# MCU009A_EmuInterface.net
KiCad netlist of a schematic drawn in Altium Designer
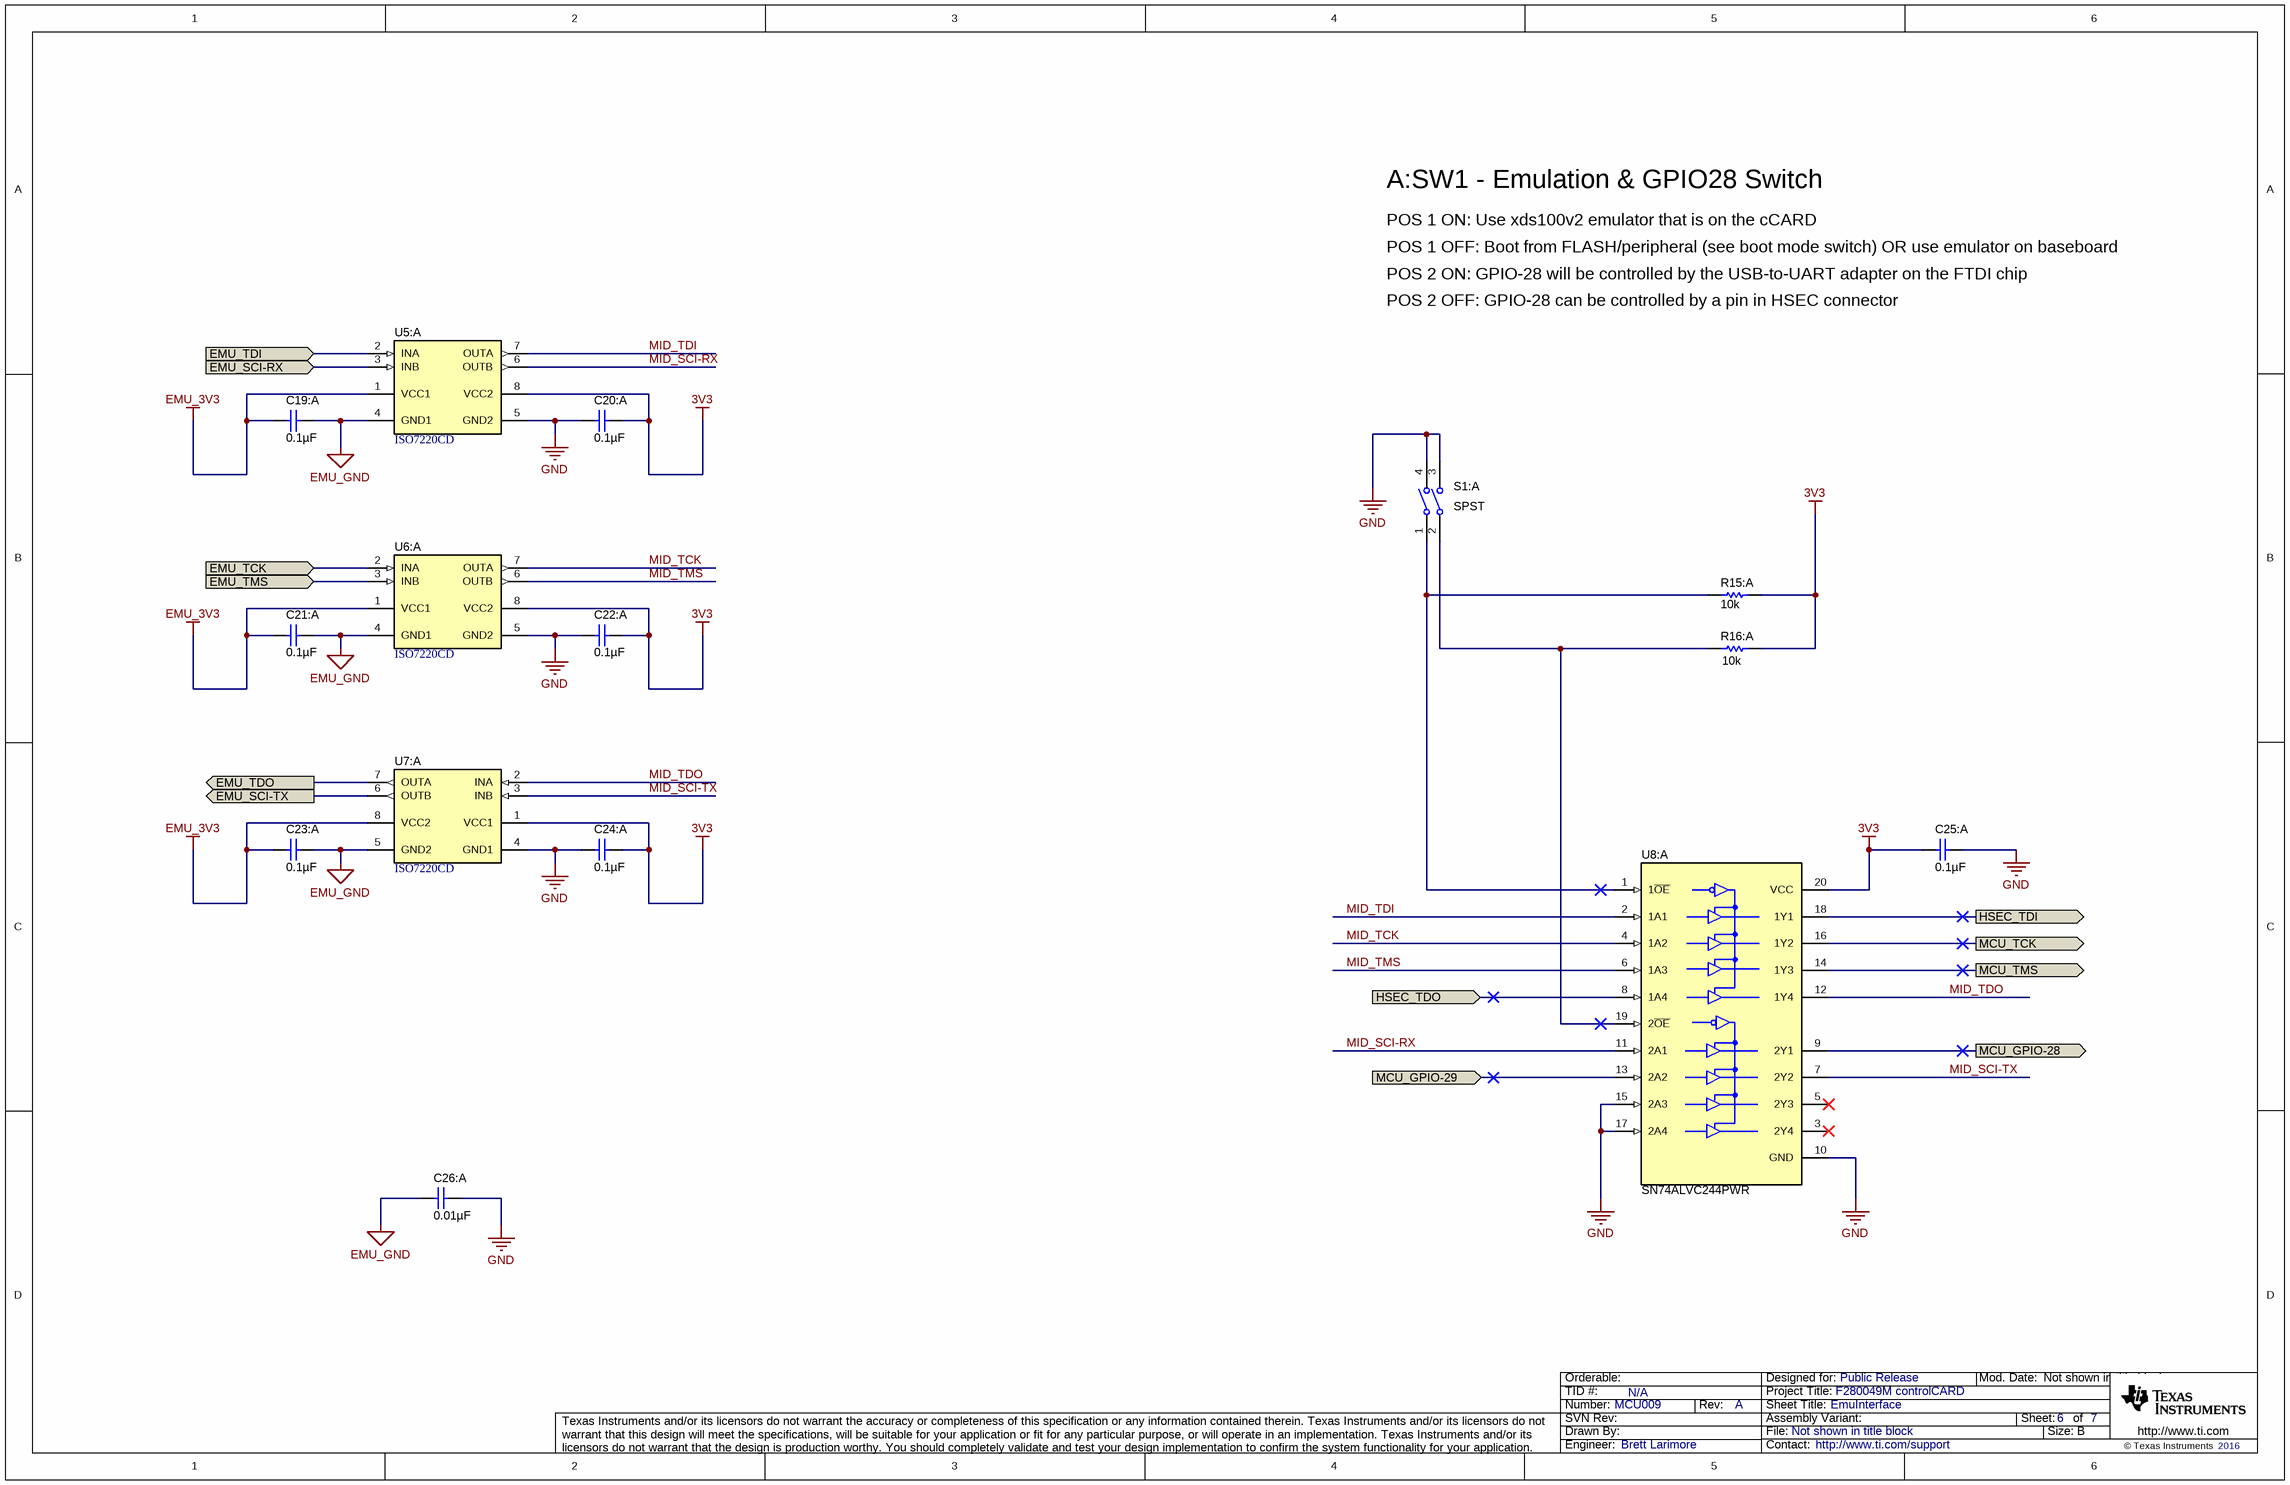
[diagram p0: MCU009A_EmuInterface.SchDoc]

(export (version "E")
  (design (tool "Eeschema 10.0.6"))
  (components
    (comp (ref "C19:A")
      (value "GRM155R71A104KA01D")
      (footprint "0402")
      (description "CAP, CERM, 0.1 µF, 10 V, +/- 10%, X7R, 0402")
      (fields
        (field (name "VALUEDISPLAYED") "0.1µF")
        (field (name "MANUFACTURER") "MuRata")
        (field (name "PUBLISHER") "Texas Instruments")
      )
      (libsource (lib "Capacitor_Ceramic") (part "GRM155R71A104KA01D"))
    )
    (comp (ref "C20:A")
      (value "GRM155R71A104KA01D")
      (footprint "0402")
      (description "CAP, CERM, 0.1 µF, 10 V, +/- 10%, X7R, 0402")
      (fields
        (field (name "VALUEDISPLAYED") "0.1µF")
        (field (name "MANUFACTURER") "MuRata")
        (field (name "PUBLISHER") "Texas Instruments")
      )
      (libsource (lib "Capacitor_Ceramic") (part "GRM155R71A104KA01D"))
    )
    (comp (ref "C21:A")
      (value "GRM155R71A104KA01D")
      (footprint "0402")
      (description "CAP, CERM, 0.1 µF, 10 V, +/- 10%, X7R, 0402")
      (fields
        (field (name "VALUEDISPLAYED") "0.1µF")
        (field (name "MANUFACTURER") "MuRata")
        (field (name "PUBLISHER") "Texas Instruments")
      )
      (libsource (lib "Capacitor_Ceramic") (part "GRM155R71A104KA01D"))
    )
    (comp (ref "C22:A")
      (value "GRM155R71A104KA01D")
      (footprint "0402")
      (description "CAP, CERM, 0.1 µF, 10 V, +/- 10%, X7R, 0402")
      (fields
        (field (name "VALUEDISPLAYED") "0.1µF")
        (field (name "MANUFACTURER") "MuRata")
        (field (name "PUBLISHER") "Texas Instruments")
      )
      (libsource (lib "Capacitor_Ceramic") (part "GRM155R71A104KA01D"))
    )
    (comp (ref "C23:A")
      (value "GRM155R71A104KA01D")
      (footprint "0402")
      (description "CAP, CERM, 0.1 µF, 10 V, +/- 10%, X7R, 0402")
      (fields
        (field (name "VALUEDISPLAYED") "0.1µF")
        (field (name "MANUFACTURER") "MuRata")
        (field (name "PUBLISHER") "Texas Instruments")
      )
      (libsource (lib "Capacitor_Ceramic") (part "GRM155R71A104KA01D"))
    )
    (comp (ref "C24:A")
      (value "GRM155R71A104KA01D")
      (footprint "0402")
      (description "CAP, CERM, 0.1 µF, 10 V, +/- 10%, X7R, 0402")
      (fields
        (field (name "VALUEDISPLAYED") "0.1µF")
        (field (name "MANUFACTURER") "MuRata")
        (field (name "PUBLISHER") "Texas Instruments")
      )
      (libsource (lib "Capacitor_Ceramic") (part "GRM155R71A104KA01D"))
    )
    (comp (ref "C25:A")
      (value "GRM155R71A104KA01D")
      (footprint "0402")
      (description "CAP, CERM, 0.1 µF, 10 V, +/- 10%, X7R, 0402")
      (fields
        (field (name "VALUEDISPLAYED") "0.1µF")
        (field (name "MANUFACTURER") "MuRata")
        (field (name "PUBLISHER") "Texas Instruments")
      )
      (libsource (lib "Capacitor_Ceramic") (part "GRM155R71A104KA01D"))
    )
    (comp (ref "C26:A")
      (value "1812SC103KAT1A")
      (footprint "1812")
      (description "CAP, CERM, 0.01 µF, 1500 V, +/- 10%, X7R, 1812")
      (fields
        (field (name "VALUEDISPLAYED") "0.01µF")
        (field (name "MANUFACTURER") "AVX")
        (field (name "PUBLISHER") "Texas Instruments")
      )
      (libsource (lib "Capacitor_Ceramic") (part "1812SC103KAT1A"))
    )
    (comp (ref "R15:A")
      (value "CRCW040210K0JNED")
      (footprint "0402")
      (description "RES, 10 k, 5%, 0.063 W, 0402")
      (fields
        (field (name "VALUEDISPLAYED") "10k")
        (field (name "MANUFACTURER") "Vishay-Dale")
        (field (name "PUBLISHER") "Texas Instruments")
      )
      (libsource (lib "Resistor_0402") (part "CRCW040210K0JNED"))
    )
    (comp (ref "R16:A")
      (value "CRCW040210K0JNED")
      (footprint "0402")
      (description "RES, 10 k, 5%, 0.063 W, 0402")
      (fields
        (field (name "VALUEDISPLAYED") "10k")
        (field (name "MANUFACTURER") "Vishay-Dale")
        (field (name "PUBLISHER") "Texas Instruments")
      )
      (libsource (lib "Resistor_0402") (part "CRCW040210K0JNED"))
    )
    (comp (ref "S1:A")
      (value "218-2LPST")
      (footprint "SW_218-2LP")
      (description "Switch, SPST, 2 Pos, 25mA, 24VDC, SMD")
      (fields
        (field (name "MANUFACTURER") "CTS Electrocomponents")
        (field (name "CIRCUIT") "SPST")
        (field (name "SYMBOLCREATOR") "Altium")
        (field (name "PUBLISHER") "Texas Instruments")
      )
      (libsource (lib "Switches") (part "218-2LPST"))
    )
    (comp (ref "U5:A")
      (value "ISO7220CD")
      (footprint "D0008A_N")
      (fields
        (field (name "MANUFACTURER") "Texas Instruments")
        (field (name "ALTERNATE PARTNUMBER") "Equivalent")
      )
      (libsource (lib "") (part "ISO7220CD_1"))
    )
    (comp (ref "U6:A")
      (value "ISO7220CD")
      (footprint "D0008A_N")
      (fields
        (field (name "MANUFACTURER") "Texas Instruments")
        (field (name "ALTERNATE PARTNUMBER") "Equivalent")
      )
      (libsource (lib "") (part "ISO7220CD_1"))
    )
    (comp (ref "U7:A")
      (value "ISO7220CD")
      (footprint "D0008A_N")
      (fields
        (field (name "MANUFACTURER") "Texas Instruments")
        (field (name "ALTERNATE PARTNUMBER") "Equivalent")
      )
      (libsource (lib "TI Interface Isolator") (part "ISO7220CD"))
    )
    (comp (ref "U8:A")
      (value "SN74ALVC244PWR")
      (footprint "PW0020A_N")
      (description "OCTAL BUFFER/DRIVER WITH 3-STATE OUTPUTS, PW0020A (TSSOP-20)")
      (fields
        (field (name "ALTERNATE PARTNUMBER") "SN74ALVC244PW")
        (field (name "MANUFACTURER") "Texas Instruments")
        (field (name "SYMBOLCREATOR") "Altium")
        (field (name "PUBLISHER") "Texas Instruments")
      )
      (libsource (lib "TI_Pre_Release1") (part "SN74ALVC244PWR"))
    )
  )
  (nets
    (net (code "1") (name "/EMU_SCI-RX") (class "Default")
      (node (ref "U5:A") (pin "3") (pinfunction "INB_3") (pintype "input"))
    )
    (net (code "2") (name "/EMU_SCI-TX") (class "Default")
      (node (ref "U7:A") (pin "6") (pinfunction "OUTB_6") (pintype "output"))
    )
    (net (code "3") (name "/EMU_TCK") (class "Default")
      (node (ref "U6:A") (pin "2") (pinfunction "INA_2") (pintype "input"))
    )
    (net (code "4") (name "/EMU_TDI") (class "Default")
      (node (ref "U5:A") (pin "2") (pinfunction "INA_2") (pintype "input"))
    )
    (net (code "5") (name "/EMU_TDO") (class "Default")
      (node (ref "U7:A") (pin "7") (pinfunction "OUTA_7") (pintype "output"))
    )
    (net (code "6") (name "/EMU_TMS") (class "Default")
      (node (ref "U6:A") (pin "3") (pinfunction "INB_3") (pintype "input"))
    )
    (net (code "7") (name "/HSEC_TDI") (class "Default")
      (node (ref "U8:A") (pin "18") (pinfunction "1Y1_18") (pintype "tri_state"))
    )
    (net (code "8") (name "/HSEC_TDO") (class "Default")
      (node (ref "U8:A") (pin "8") (pinfunction "1A4_8") (pintype "input"))
    )
    (net (code "9") (name "/MCU_GPIO-28") (class "Default")
      (node (ref "U8:A") (pin "9") (pinfunction "2Y1_9") (pintype "tri_state"))
    )
    (net (code "10") (name "/MCU_GPIO-29") (class "Default")
      (node (ref "U8:A") (pin "13") (pinfunction "2A2_13") (pintype "input"))
    )
    (net (code "11") (name "/MCU_TCK") (class "Default")
      (node (ref "U8:A") (pin "16") (pinfunction "1Y2_16") (pintype "tri_state"))
    )
    (net (code "12") (name "/MCU_TMS") (class "Default")
      (node (ref "U8:A") (pin "14") (pinfunction "1Y3_14") (pintype "tri_state"))
    )
    (net (code "13") (name "/MID_SCI-RX") (class "Default")
      (node (ref "U5:A") (pin "6") (pinfunction "OUTB_6") (pintype "output"))
      (node (ref "U8:A") (pin "11") (pinfunction "2A1_11") (pintype "input"))
    )
    (net (code "14") (name "/MID_SCI-TX") (class "Default")
      (node (ref "U7:A") (pin "3") (pinfunction "INB_3") (pintype "input"))
      (node (ref "U8:A") (pin "7") (pinfunction "2Y2_7") (pintype "tri_state"))
    )
    (net (code "15") (name "/MID_TCK") (class "Default")
      (node (ref "U6:A") (pin "7") (pinfunction "OUTA_7") (pintype "output"))
      (node (ref "U8:A") (pin "4") (pinfunction "1A2_4") (pintype "input"))
    )
    (net (code "16") (name "/MID_TDI") (class "Default")
      (node (ref "U5:A") (pin "7") (pinfunction "OUTA_7") (pintype "output"))
      (node (ref "U8:A") (pin "2") (pinfunction "1A1_2") (pintype "input"))
    )
    (net (code "17") (name "/MID_TDO") (class "Default")
      (node (ref "U7:A") (pin "2") (pinfunction "INA_2") (pintype "input"))
      (node (ref "U8:A") (pin "12") (pinfunction "1Y4_12") (pintype "tri_state"))
    )
    (net (code "18") (name "/MID_TMS") (class "Default")
      (node (ref "U6:A") (pin "6") (pinfunction "OUTB_6") (pintype "output"))
      (node (ref "U8:A") (pin "6") (pinfunction "1A3_6") (pintype "input"))
    )
    (net (code "19") (name "3V3") (class "Default")
      (node (ref "C20:A") (pin "1") (pinfunction "1_1") (pintype "passive"))
      (node (ref "C22:A") (pin "1") (pinfunction "1_1") (pintype "passive"))
      (node (ref "C24:A") (pin "1") (pinfunction "1_1") (pintype "passive"))
      (node (ref "C25:A") (pin "2") (pinfunction "2_2") (pintype "passive"))
      (node (ref "R15:A") (pin "2") (pinfunction "2_2") (pintype "passive"))
      (node (ref "R16:A") (pin "2") (pinfunction "2_2") (pintype "passive"))
      (node (ref "U5:A") (pin "8") (pinfunction "VCC2_8") (pintype "power_in"))
      (node (ref "U6:A") (pin "8") (pinfunction "VCC2_8") (pintype "power_in"))
      (node (ref "U7:A") (pin "1") (pinfunction "VCC1_1") (pintype "power_in"))
      (node (ref "U8:A") (pin "20") (pinfunction "VCC_20") (pintype "power_in"))
    )
    (net (code "20") (name "EMU_3V3") (class "Default")
      (node (ref "C19:A") (pin "2") (pinfunction "2_2") (pintype "passive"))
      (node (ref "C21:A") (pin "2") (pinfunction "2_2") (pintype "passive"))
      (node (ref "C23:A") (pin "2") (pinfunction "2_2") (pintype "passive"))
      (node (ref "U5:A") (pin "1") (pinfunction "VCC1_1") (pintype "power_in"))
      (node (ref "U6:A") (pin "1") (pinfunction "VCC1_1") (pintype "power_in"))
      (node (ref "U7:A") (pin "8") (pinfunction "VCC2_8") (pintype "power_in"))
    )
    (net (code "21") (name "EMU_GND") (class "Default")
      (node (ref "C19:A") (pin "1") (pinfunction "1_1") (pintype "passive"))
      (node (ref "C21:A") (pin "1") (pinfunction "1_1") (pintype "passive"))
      (node (ref "C23:A") (pin "1") (pinfunction "1_1") (pintype "passive"))
      (node (ref "C26:A") (pin "2") (pinfunction "2_2") (pintype "passive"))
      (node (ref "U5:A") (pin "4") (pinfunction "GND1_4") (pintype "power_in"))
      (node (ref "U6:A") (pin "4") (pinfunction "GND1_4") (pintype "power_in"))
      (node (ref "U7:A") (pin "5") (pinfunction "GND2_5") (pintype "power_in"))
    )
    (net (code "22") (name "GND") (class "Default")
      (node (ref "C20:A") (pin "2") (pinfunction "2_2") (pintype "passive"))
      (node (ref "C22:A") (pin "2") (pinfunction "2_2") (pintype "passive"))
      (node (ref "C24:A") (pin "2") (pinfunction "2_2") (pintype "passive"))
      (node (ref "C25:A") (pin "1") (pinfunction "1_1") (pintype "passive"))
      (node (ref "C26:A") (pin "1") (pinfunction "1_1") (pintype "passive"))
      (node (ref "S1:A") (pin "3") (pinfunction "3_3") (pintype "passive"))
      (node (ref "S1:A") (pin "4") (pinfunction "4_4") (pintype "passive"))
      (node (ref "U5:A") (pin "5") (pinfunction "GND2_5") (pintype "power_in"))
      (node (ref "U6:A") (pin "5") (pinfunction "GND2_5") (pintype "power_in"))
      (node (ref "U7:A") (pin "4") (pinfunction "GND1_4") (pintype "power_in"))
      (node (ref "U8:A") (pin "10") (pinfunction "GND_10") (pintype "power_in"))
      (node (ref "U8:A") (pin "15") (pinfunction "2A3_15") (pintype "input"))
      (node (ref "U8:A") (pin "17") (pinfunction "2A4_17") (pintype "input"))
    )
    (net (code "23") (name "Net-(U8:A-1~{OE})") (class "Default")
      (node (ref "R15:A") (pin "1") (pinfunction "1_1") (pintype "passive"))
      (node (ref "S1:A") (pin "1") (pinfunction "1_1") (pintype "passive"))
      (node (ref "U8:A") (pin "1") (pinfunction "1~{OE}_1") (pintype "input"))
    )
    (net (code "24") (name "Net-(U8:A-2~{OE})") (class "Default")
      (node (ref "R16:A") (pin "1") (pinfunction "1_1") (pintype "passive"))
      (node (ref "S1:A") (pin "2") (pinfunction "2_2") (pintype "passive"))
      (node (ref "U8:A") (pin "19") (pinfunction "2~{OE}_19") (pintype "input"))
    )
    (net (code "25") (name "unconnected-(U8:A-2Y3-Pad5)") (class "Default")
      (node (ref "U8:A") (pin "5") (pinfunction "2Y3_5") (pintype "tri_state+no_connect"))
    )
    (net (code "26") (name "unconnected-(U8:A-2Y4-Pad3)") (class "Default")
      (node (ref "U8:A") (pin "3") (pinfunction "2Y4_3") (pintype "tri_state+no_connect"))
    )
  )
)
